# OSSI-1_Z_Panel.net
KiCad netlist of a schematic drawn in EAGLE
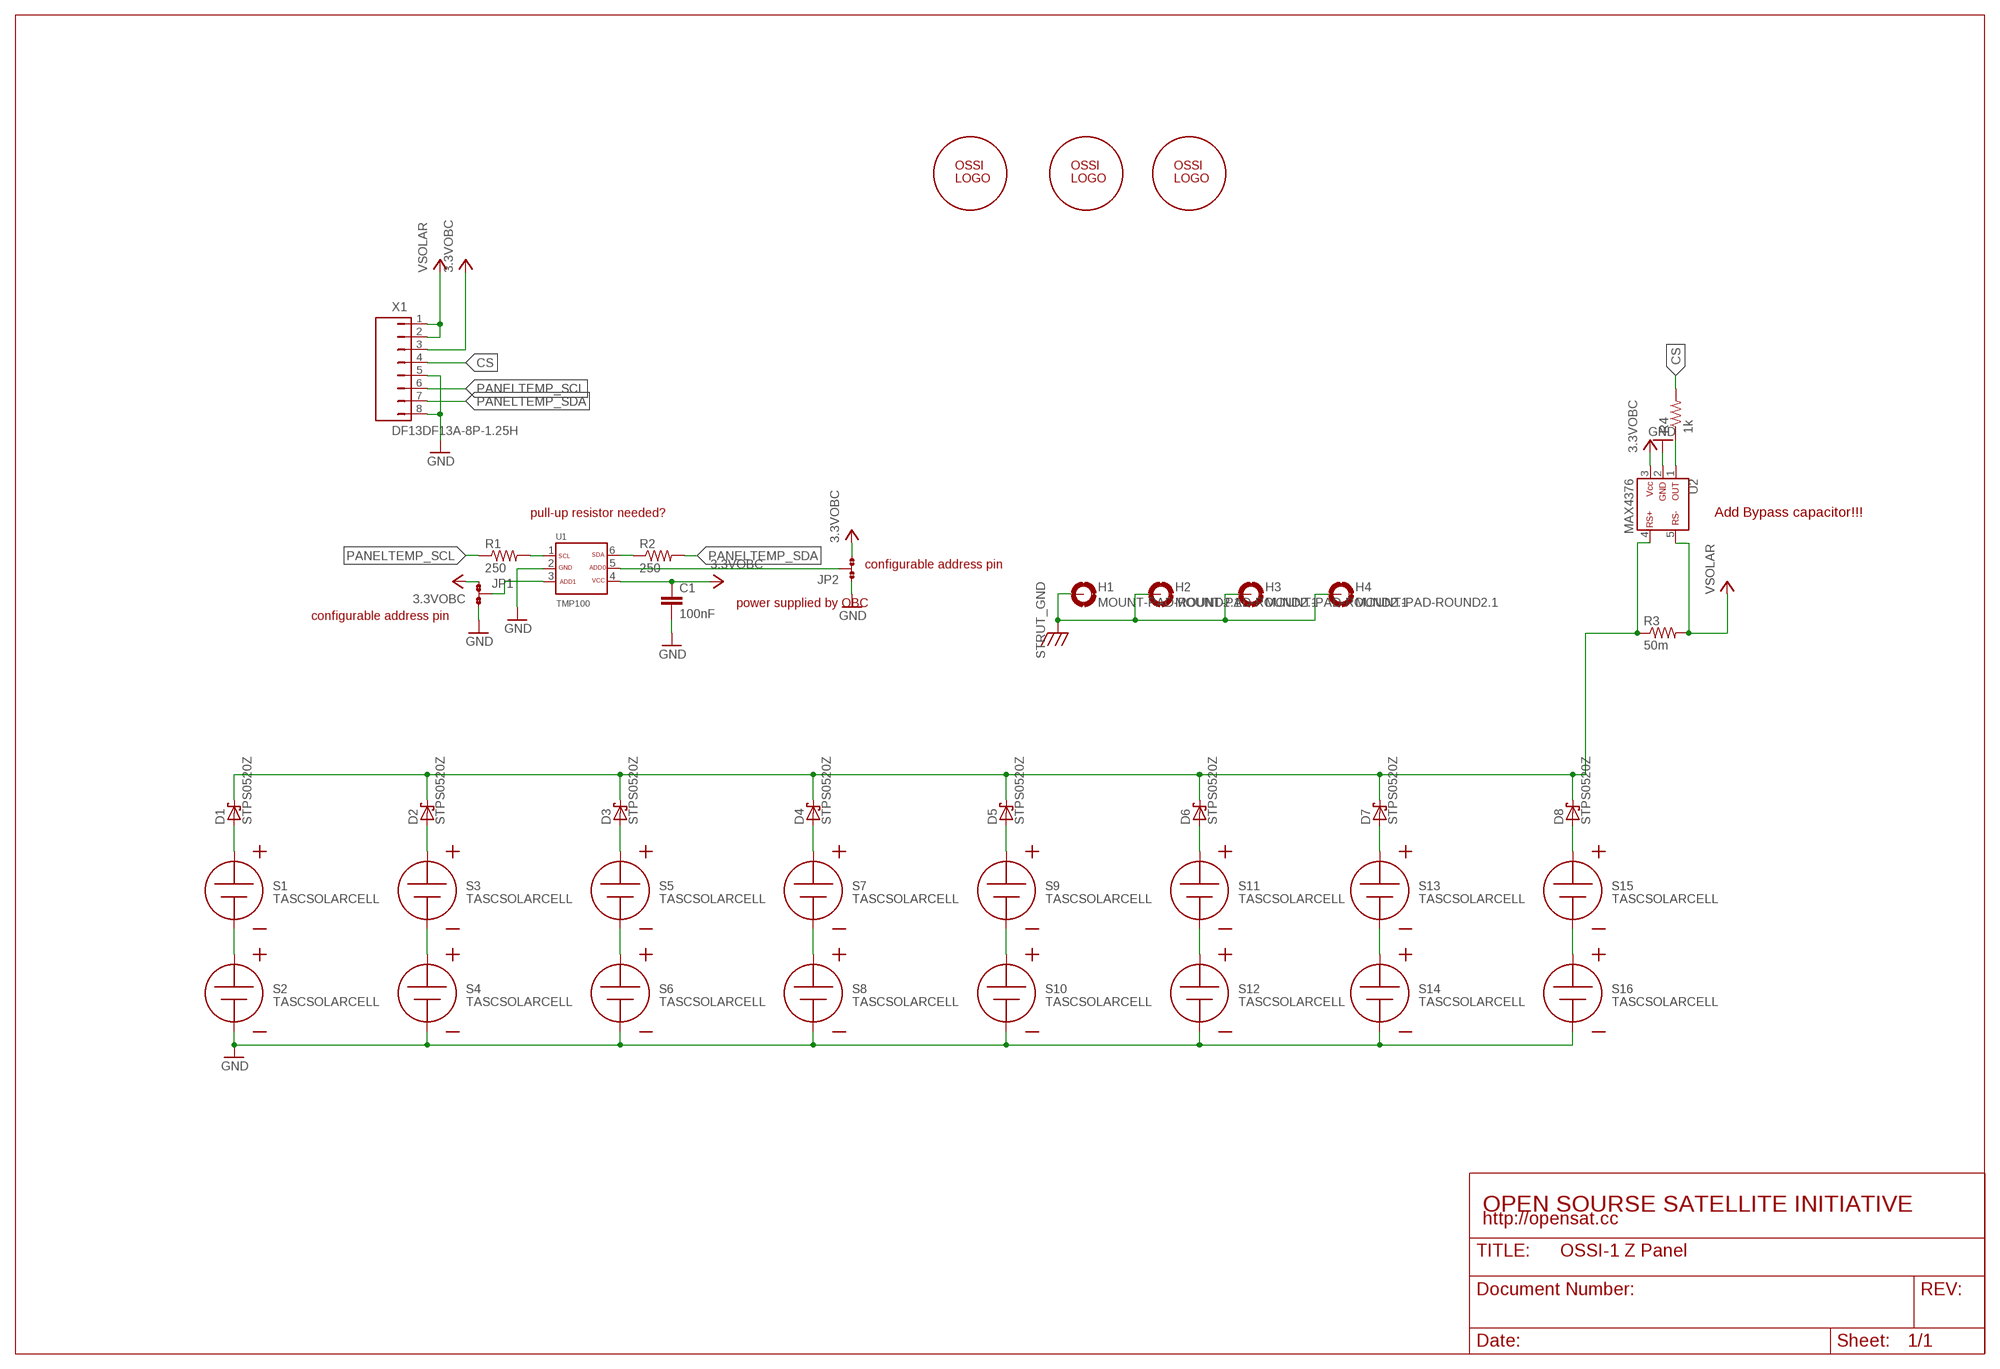
[diagram p0: schematic, sheet 1]

(export (version "E")
  (design (tool "Eeschema 10.0.6"))
  (components
    (comp (ref "C1")
      (value "100nF")
      (footprint "eagle-import:C0603(1608)")
      (libsource (lib "eagle-import") (part "C0603(1608)"))
    )
    (comp (ref "D1")
      (value "STPS0520Z")
      (footprint "eagle-import:SOD-123")
      (libsource (lib "eagle-import") (part "STPS0520Z"))
    )
    (comp (ref "D2")
      (value "STPS0520Z")
      (footprint "eagle-import:SOD-123")
      (libsource (lib "eagle-import") (part "STPS0520Z"))
    )
    (comp (ref "D3")
      (value "STPS0520Z")
      (footprint "eagle-import:SOD-123")
      (libsource (lib "eagle-import") (part "STPS0520Z"))
    )
    (comp (ref "D4")
      (value "STPS0520Z")
      (footprint "eagle-import:SOD-123")
      (libsource (lib "eagle-import") (part "STPS0520Z"))
    )
    (comp (ref "D5")
      (value "STPS0520Z")
      (footprint "eagle-import:SOD-123")
      (libsource (lib "eagle-import") (part "STPS0520Z"))
    )
    (comp (ref "D6")
      (value "STPS0520Z")
      (footprint "eagle-import:SOD-123")
      (libsource (lib "eagle-import") (part "STPS0520Z"))
    )
    (comp (ref "D7")
      (value "STPS0520Z")
      (footprint "eagle-import:SOD-123")
      (libsource (lib "eagle-import") (part "STPS0520Z"))
    )
    (comp (ref "D8")
      (value "STPS0520Z")
      (footprint "eagle-import:SOD-123")
      (libsource (lib "eagle-import") (part "STPS0520Z"))
    )
    (comp (ref "H1")
      (value "MOUNT-PAD-ROUND2.1")
      (footprint "eagle-import:2.1-PAD-ROUND")
      (libsource (lib "eagle-import") (part "MOUNT-PAD-ROUND2.1"))
    )
    (comp (ref "H2")
      (value "MOUNT-PAD-ROUND2.1")
      (footprint "eagle-import:2.1-PAD-ROUND")
      (libsource (lib "eagle-import") (part "MOUNT-PAD-ROUND2.1"))
    )
    (comp (ref "H3")
      (value "MOUNT-PAD-ROUND2.1")
      (footprint "eagle-import:2.1-PAD-ROUND")
      (libsource (lib "eagle-import") (part "MOUNT-PAD-ROUND2.1"))
    )
    (comp (ref "H4")
      (value "MOUNT-PAD-ROUND2.1")
      (footprint "eagle-import:2.1-PAD-ROUND")
      (libsource (lib "eagle-import") (part "MOUNT-PAD-ROUND2.1"))
    )
    (comp (ref "JP1")
      (value "JP2")
      (footprint "eagle-import:JP2SMD0603")
      (libsource (lib "eagle-import") (part "JP2"))
    )
    (comp (ref "JP2")
      (value "JP2")
      (footprint "eagle-import:JP2SMD0603")
      (libsource (lib "eagle-import") (part "JP2"))
    )
    (comp (ref "R1")
      (value "250")
      (footprint "eagle-import:R0603(1608)")
      (libsource (lib "eagle-import") (part "R0603(1608)"))
    )
    (comp (ref "R2")
      (value "250")
      (footprint "eagle-import:R0603(1608)")
      (libsource (lib "eagle-import") (part "R0603(1608)"))
    )
    (comp (ref "R3")
      (value "50m")
      (footprint "eagle-import:WSL1206")
      (libsource (lib "eagle-import") (part "RWSL1206"))
    )
    (comp (ref "R4")
      (value "1k")
      (footprint "eagle-import:R0603(1608)")
      (libsource (lib "eagle-import") (part "R0603(1608)"))
    )
    (comp (ref "S1")
      (value "TASCSOLARCELL")
      (footprint "eagle-import:TASCSOLARCELL")
      (libsource (lib "eagle-import") (part "TASCSOLARCELL"))
    )
    (comp (ref "S2")
      (value "TASCSOLARCELL")
      (footprint "eagle-import:TASCSOLARCELL")
      (libsource (lib "eagle-import") (part "TASCSOLARCELL"))
    )
    (comp (ref "S3")
      (value "TASCSOLARCELL")
      (footprint "eagle-import:TASCSOLARCELL")
      (libsource (lib "eagle-import") (part "TASCSOLARCELL"))
    )
    (comp (ref "S4")
      (value "TASCSOLARCELL")
      (footprint "eagle-import:TASCSOLARCELL")
      (libsource (lib "eagle-import") (part "TASCSOLARCELL"))
    )
    (comp (ref "S5")
      (value "TASCSOLARCELL")
      (footprint "eagle-import:TASCSOLARCELL")
      (libsource (lib "eagle-import") (part "TASCSOLARCELL"))
    )
    (comp (ref "S6")
      (value "TASCSOLARCELL")
      (footprint "eagle-import:TASCSOLARCELL")
      (libsource (lib "eagle-import") (part "TASCSOLARCELL"))
    )
    (comp (ref "S7")
      (value "TASCSOLARCELL")
      (footprint "eagle-import:TASCSOLARCELL")
      (libsource (lib "eagle-import") (part "TASCSOLARCELL"))
    )
    (comp (ref "S8")
      (value "TASCSOLARCELL")
      (footprint "eagle-import:TASCSOLARCELL")
      (libsource (lib "eagle-import") (part "TASCSOLARCELL"))
    )
    (comp (ref "S9")
      (value "TASCSOLARCELL")
      (footprint "eagle-import:TASCSOLARCELL")
      (libsource (lib "eagle-import") (part "TASCSOLARCELL"))
    )
    (comp (ref "S10")
      (value "TASCSOLARCELL")
      (footprint "eagle-import:TASCSOLARCELL")
      (libsource (lib "eagle-import") (part "TASCSOLARCELL"))
    )
    (comp (ref "S11")
      (value "TASCSOLARCELL")
      (footprint "eagle-import:TASCSOLARCELL")
      (libsource (lib "eagle-import") (part "TASCSOLARCELL"))
    )
    (comp (ref "S12")
      (value "TASCSOLARCELL")
      (footprint "eagle-import:TASCSOLARCELL")
      (libsource (lib "eagle-import") (part "TASCSOLARCELL"))
    )
    (comp (ref "S13")
      (value "TASCSOLARCELL")
      (footprint "eagle-import:TASCSOLARCELL")
      (libsource (lib "eagle-import") (part "TASCSOLARCELL"))
    )
    (comp (ref "S14")
      (value "TASCSOLARCELL")
      (footprint "eagle-import:TASCSOLARCELL")
      (libsource (lib "eagle-import") (part "TASCSOLARCELL"))
    )
    (comp (ref "S15")
      (value "TASCSOLARCELL")
      (footprint "eagle-import:TASCSOLARCELL")
      (libsource (lib "eagle-import") (part "TASCSOLARCELL"))
    )
    (comp (ref "S16")
      (value "TASCSOLARCELL")
      (footprint "eagle-import:TASCSOLARCELL")
      (libsource (lib "eagle-import") (part "TASCSOLARCELL"))
    )
    (comp (ref "U$1")
      (value "OSSILOGO-10")
      (footprint "eagle-import:OSSILOGO1010")
      (libsource (lib "eagle-import") (part "OSSILOGO-10"))
    )
    (comp (ref "U$2")
      (value "OSSILOGO-10")
      (footprint "eagle-import:OSSILOGO1010")
      (libsource (lib "eagle-import") (part "OSSILOGO-10"))
    )
    (comp (ref "U$3")
      (value "OSSITAGCC")
      (footprint "eagle-import:CCLOGO")
      (libsource (lib "eagle-import") (part "OSSITAGCC"))
    )
    (comp (ref "U1")
      (value "TMP100")
      (footprint "eagle-import:SOT23-6DBV")
      (libsource (lib "eagle-import") (part "TMP100"))
    )
    (comp (ref "U2")
      (value "MAX4376")
      (footprint "eagle-import:SOT23-5DBV")
      (libsource (lib "eagle-import") (part "MAX4376"))
    )
    (comp (ref "X1")
      (value "DF13DF13A-8P-1.25H")
      (footprint "eagle-import:DF13A-8P")
      (libsource (lib "eagle-import") (part "DF13DF13A-8P-1.25H"))
    )
  )
  (nets
    (net (code "1") (name "3.3VOBC") (class "Default")
      (node (ref "C1") (pin "1") (pinfunction "1_1") (pintype "passive"))
      (node (ref "JP1") (pin "1") (pinfunction "1_1") (pintype "passive"))
      (node (ref "JP2") (pin "3") (pinfunction "3_3") (pintype "passive"))
      (node (ref "U1") (pin "4") (pinfunction "4_4") (pintype "bidirectional"))
      (node (ref "U2") (pin "3") (pinfunction "P$3_3") (pintype "power_in"))
      (node (ref "X1") (pin "3") (pinfunction "3_3") (pintype "passive"))
    )
    (net (code "2") (name "CS") (class "Default")
      (node (ref "R4") (pin "2") (pinfunction "2_2") (pintype "passive"))
      (node (ref "X1") (pin "4") (pinfunction "4_4") (pintype "passive"))
    )
    (net (code "3") (name "GND") (class "Default")
      (node (ref "C1") (pin "2") (pinfunction "2_2") (pintype "passive"))
      (node (ref "JP1") (pin "3") (pinfunction "3_3") (pintype "passive"))
      (node (ref "JP2") (pin "1") (pinfunction "1_1") (pintype "passive"))
      (node (ref "S10") (pin "N") (pinfunction "N_N") (pintype "power_in"))
      (node (ref "S12") (pin "N") (pinfunction "N_N") (pintype "power_in"))
      (node (ref "S14") (pin "N") (pinfunction "N_N") (pintype "power_in"))
      (node (ref "S16") (pin "N") (pinfunction "N_N") (pintype "power_in"))
      (node (ref "S2") (pin "N") (pinfunction "N_N") (pintype "power_in"))
      (node (ref "S4") (pin "N") (pinfunction "N_N") (pintype "power_in"))
      (node (ref "S6") (pin "N") (pinfunction "N_N") (pintype "power_in"))
      (node (ref "S8") (pin "N") (pinfunction "N_N") (pintype "power_in"))
      (node (ref "U1") (pin "2") (pinfunction "2_2") (pintype "bidirectional"))
      (node (ref "U2") (pin "2") (pinfunction "P$2_2") (pintype "power_in"))
      (node (ref "X1") (pin "5") (pinfunction "5_5") (pintype "passive"))
      (node (ref "X1") (pin "8") (pinfunction "8_8") (pintype "passive"))
    )
    (net (code "4") (name "Net-(D1-PadA)") (class "Default")
      (node (ref "D1") (pin "A") (pinfunction "A_A") (pintype "passive"))
      (node (ref "S1") (pin "P") (pinfunction "P_P") (pintype "power_in"))
    )
    (net (code "5") (name "Net-(D2-PadA)") (class "Default")
      (node (ref "D2") (pin "A") (pinfunction "A_A") (pintype "passive"))
      (node (ref "S3") (pin "P") (pinfunction "P_P") (pintype "power_in"))
    )
    (net (code "6") (name "Net-(D3-PadA)") (class "Default")
      (node (ref "D3") (pin "A") (pinfunction "A_A") (pintype "passive"))
      (node (ref "S5") (pin "P") (pinfunction "P_P") (pintype "power_in"))
    )
    (net (code "7") (name "Net-(D4-PadA)") (class "Default")
      (node (ref "D4") (pin "A") (pinfunction "A_A") (pintype "passive"))
      (node (ref "S7") (pin "P") (pinfunction "P_P") (pintype "power_in"))
    )
    (net (code "8") (name "Net-(D5-PadA)") (class "Default")
      (node (ref "D5") (pin "A") (pinfunction "A_A") (pintype "passive"))
      (node (ref "S9") (pin "P") (pinfunction "P_P") (pintype "power_in"))
    )
    (net (code "9") (name "Net-(D6-PadA)") (class "Default")
      (node (ref "D6") (pin "A") (pinfunction "A_A") (pintype "passive"))
      (node (ref "S11") (pin "P") (pinfunction "P_P") (pintype "power_in"))
    )
    (net (code "10") (name "Net-(D7-PadA)") (class "Default")
      (node (ref "D7") (pin "A") (pinfunction "A_A") (pintype "passive"))
      (node (ref "S13") (pin "P") (pinfunction "P_P") (pintype "power_in"))
    )
    (net (code "11") (name "Net-(D8-PadA)") (class "Default")
      (node (ref "D8") (pin "A") (pinfunction "A_A") (pintype "passive"))
      (node (ref "S15") (pin "P") (pinfunction "P_P") (pintype "power_in"))
    )
    (net (code "12") (name "Net-(JP1-Pad2)") (class "Default")
      (node (ref "JP1") (pin "2") (pinfunction "2_2") (pintype "passive"))
      (node (ref "U1") (pin "3") (pinfunction "3_3") (pintype "bidirectional"))
    )
    (net (code "13") (name "Net-(JP2-Pad2)") (class "Default")
      (node (ref "JP2") (pin "2") (pinfunction "2_2") (pintype "passive"))
      (node (ref "U1") (pin "5") (pinfunction "5_5") (pintype "bidirectional"))
    )
    (net (code "14") (name "Net-(R1-Pad2)") (class "Default")
      (node (ref "R1") (pin "2") (pinfunction "2_2") (pintype "passive"))
      (node (ref "U1") (pin "1") (pinfunction "1_1") (pintype "bidirectional"))
    )
    (net (code "15") (name "Net-(R2-Pad1)") (class "Default")
      (node (ref "R2") (pin "1") (pinfunction "1_1") (pintype "passive"))
      (node (ref "U1") (pin "6") (pinfunction "6_6") (pintype "bidirectional"))
    )
    (net (code "16") (name "Net-(R3-1)") (class "Default")
      (node (ref "D1") (pin "C") (pinfunction "C_C") (pintype "passive"))
      (node (ref "D2") (pin "C") (pinfunction "C_C") (pintype "passive"))
      (node (ref "D3") (pin "C") (pinfunction "C_C") (pintype "passive"))
      (node (ref "D4") (pin "C") (pinfunction "C_C") (pintype "passive"))
      (node (ref "D5") (pin "C") (pinfunction "C_C") (pintype "passive"))
      (node (ref "D6") (pin "C") (pinfunction "C_C") (pintype "passive"))
      (node (ref "D7") (pin "C") (pinfunction "C_C") (pintype "passive"))
      (node (ref "D8") (pin "C") (pinfunction "C_C") (pintype "passive"))
      (node (ref "R3") (pin "P$1") (pinfunction "1_P$1") (pintype "passive"))
      (node (ref "U2") (pin "4") (pinfunction "P$4_4") (pintype "input"))
    )
    (net (code "17") (name "Net-(S1-PadN)") (class "Default")
      (node (ref "S1") (pin "N") (pinfunction "N_N") (pintype "power_in"))
      (node (ref "S2") (pin "P") (pinfunction "P_P") (pintype "power_in"))
    )
    (net (code "18") (name "Net-(S3-PadN)") (class "Default")
      (node (ref "S3") (pin "N") (pinfunction "N_N") (pintype "power_in"))
      (node (ref "S4") (pin "P") (pinfunction "P_P") (pintype "power_in"))
    )
    (net (code "19") (name "Net-(S5-PadN)") (class "Default")
      (node (ref "S5") (pin "N") (pinfunction "N_N") (pintype "power_in"))
      (node (ref "S6") (pin "P") (pinfunction "P_P") (pintype "power_in"))
    )
    (net (code "20") (name "Net-(S7-PadN)") (class "Default")
      (node (ref "S7") (pin "N") (pinfunction "N_N") (pintype "power_in"))
      (node (ref "S8") (pin "P") (pinfunction "P_P") (pintype "power_in"))
    )
    (net (code "21") (name "Net-(S10-PadP)") (class "Default")
      (node (ref "S10") (pin "P") (pinfunction "P_P") (pintype "power_in"))
      (node (ref "S9") (pin "N") (pinfunction "N_N") (pintype "power_in"))
    )
    (net (code "22") (name "Net-(S11-PadN)") (class "Default")
      (node (ref "S11") (pin "N") (pinfunction "N_N") (pintype "power_in"))
      (node (ref "S12") (pin "P") (pinfunction "P_P") (pintype "power_in"))
    )
    (net (code "23") (name "Net-(S13-PadN)") (class "Default")
      (node (ref "S13") (pin "N") (pinfunction "N_N") (pintype "power_in"))
      (node (ref "S14") (pin "P") (pinfunction "P_P") (pintype "power_in"))
    )
    (net (code "24") (name "Net-(S15-PadN)") (class "Default")
      (node (ref "S15") (pin "N") (pinfunction "N_N") (pintype "power_in"))
      (node (ref "S16") (pin "P") (pinfunction "P_P") (pintype "power_in"))
    )
    (net (code "25") (name "Net-(U2-P$1)") (class "Default")
      (node (ref "R4") (pin "1") (pinfunction "1_1") (pintype "passive"))
      (node (ref "U2") (pin "1") (pinfunction "P$1_1") (pintype "output"))
    )
    (net (code "26") (name "PANELTEMP_SCL") (class "Default")
      (node (ref "R1") (pin "1") (pinfunction "1_1") (pintype "passive"))
      (node (ref "X1") (pin "6") (pinfunction "6_6") (pintype "passive"))
    )
    (net (code "27") (name "PANELTEMP_SDA") (class "Default")
      (node (ref "R2") (pin "2") (pinfunction "2_2") (pintype "passive"))
      (node (ref "X1") (pin "7") (pinfunction "7_7") (pintype "passive"))
    )
    (net (code "28") (name "STRUT_GND") (class "Default")
      (node (ref "H1") (pin "B3,2") (pinfunction "MOUNT_B3,2") (pintype "passive"))
      (node (ref "H2") (pin "B3,2") (pinfunction "MOUNT_B3,2") (pintype "passive"))
      (node (ref "H3") (pin "B3,2") (pinfunction "MOUNT_B3,2") (pintype "passive"))
      (node (ref "H4") (pin "B3,2") (pinfunction "MOUNT_B3,2") (pintype "passive"))
    )
    (net (code "29") (name "VSOLAR") (class "Default")
      (node (ref "R3") (pin "P$2") (pinfunction "2_P$2") (pintype "passive"))
      (node (ref "U2") (pin "5") (pinfunction "P$5_5") (pintype "input"))
      (node (ref "X1") (pin "1") (pinfunction "1_1") (pintype "passive"))
      (node (ref "X1") (pin "2") (pinfunction "2_2") (pintype "passive"))
    )
  )
)
